# Power_Regulators_Digital_2.net
KiCad netlist of a schematic drawn in Altium Designer
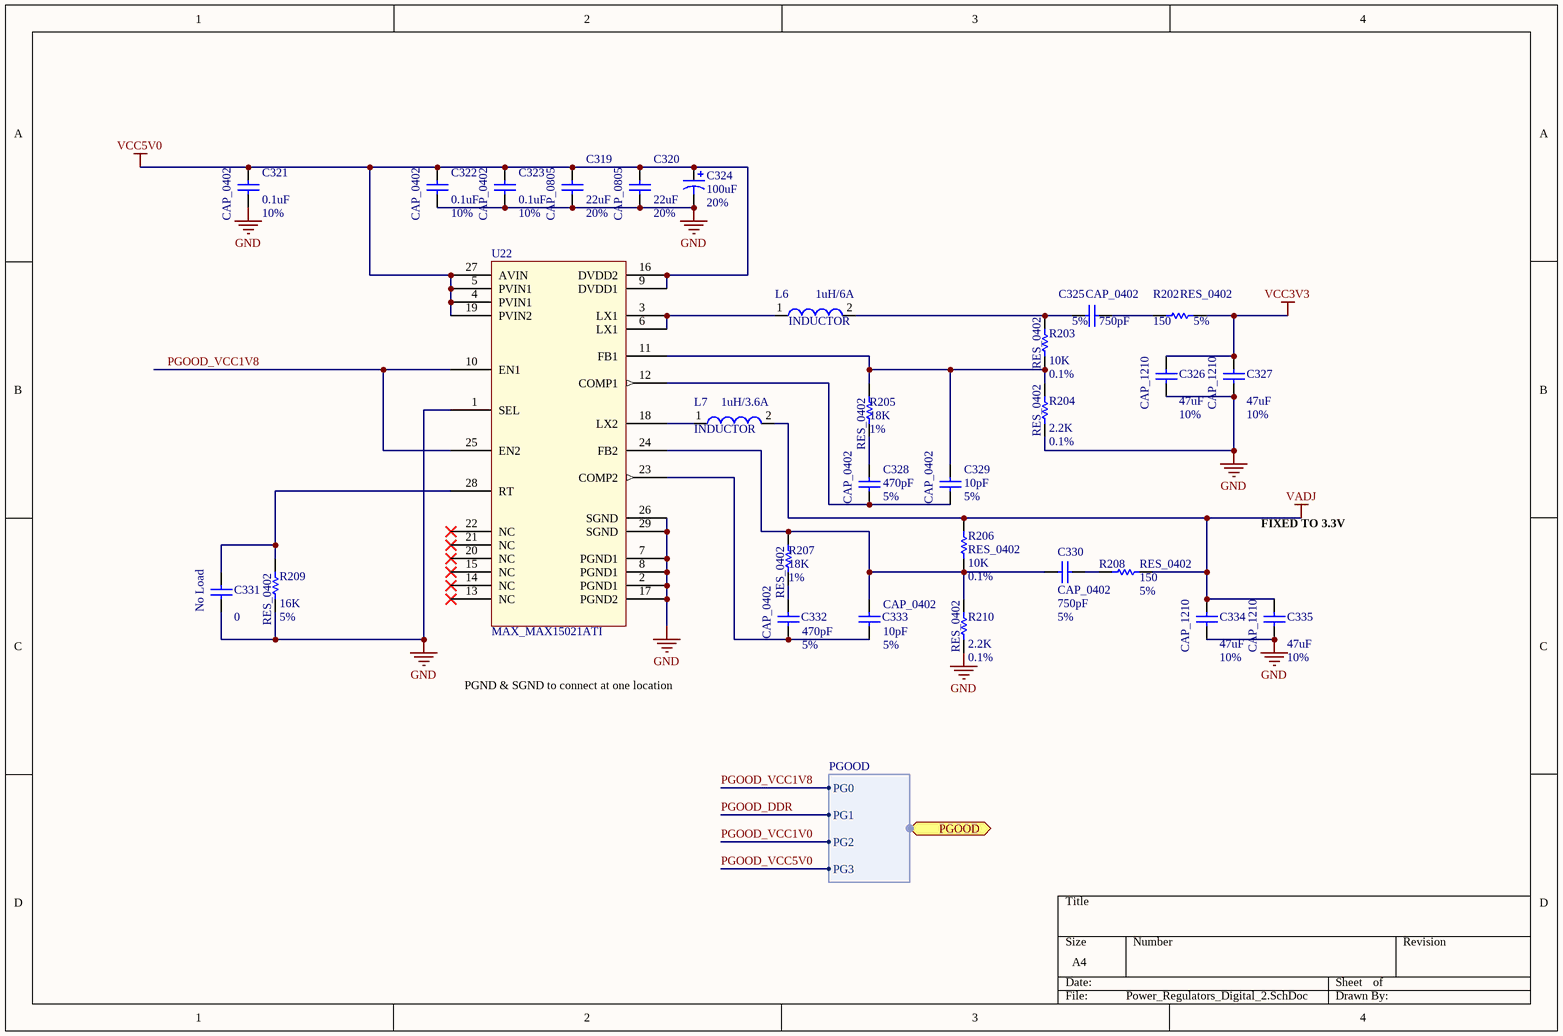
[diagram p0: Power_Regulators_Digital_2.SchDoc]

(export (version "E")
  (design (tool "Eeschema 10.0.6"))
  (components
    (comp (ref "C319")
      (value "CAP_0805")
      (footprint "CAPC0805(2012)75_N")
      (description "22uF, ceramic, 20%, 6.3V, X5R, 0805")
      (fields
        (field (name "ALTIUM_VALUE") "22uF")
        (field (name "TOLERANCE") "20%")
        (field (name "PART NUMBER") "JMK212BJ226MG-T")
        (field (name "MANUFACTURER") "Taiyo Yuden")
      )
      (libsource (lib "COMRAD_Database") (part "CAP_0805"))
    )
    (comp (ref "C320")
      (value "CAP_0805")
      (footprint "CAPC0805(2012)75_N")
      (description "22uF, ceramic, 20%, 6.3V, X5R, 0805")
      (fields
        (field (name "ALTIUM_VALUE") "22uF")
        (field (name "TOLERANCE") "20%")
        (field (name "PART NUMBER") "JMK212BJ226MG-T")
        (field (name "MANUFACTURER") "Taiyo Yuden")
      )
      (libsource (lib "COMRAD_Database") (part "CAP_0805"))
    )
    (comp (ref "C321")
      (value "CAP_0402")
      (footprint "CAPC0402(1005)60_N")
      (description "0.1uf, ceramic, 10%, 6.3V, X5R, 0402")
      (fields
        (field (name "ALTIUM_VALUE") "0.1uF")
        (field (name "TOLERANCE") "10%")
        (field (name "PART NUMBER") "C1005X5R0J104K")
        (field (name "MANUFACTURER") "TDK Corporation")
      )
      (libsource (lib "COMRAD_Database") (part "CAP_0402"))
    )
    (comp (ref "C322")
      (value "CAP_0402")
      (footprint "CAPC0402(1005)60_N")
      (description "0.1uf, ceramic, 10%, 6.3V, X5R, 0402")
      (fields
        (field (name "ALTIUM_VALUE") "0.1uF")
        (field (name "TOLERANCE") "10%")
        (field (name "PART NUMBER") "C1005X5R0J104K")
        (field (name "MANUFACTURER") "TDK Corporation")
      )
      (libsource (lib "COMRAD_Database") (part "CAP_0402"))
    )
    (comp (ref "C323")
      (value "CAP_0402")
      (footprint "CAPC0402(1005)60_N")
      (description "0.1uf, ceramic, 10%, 6.3V, X5R, 0402")
      (fields
        (field (name "ALTIUM_VALUE") "0.1uF")
        (field (name "TOLERANCE") "10%")
        (field (name "PART NUMBER") "C1005X5R0J104K")
        (field (name "MANUFACTURER") "TDK Corporation")
      )
      (libsource (lib "COMRAD_Database") (part "CAP_0402"))
    )
    (comp (ref "C324")
      (value "100uF")
      (footprint "Polarized_CAPC1210(3225)")
      (description "100uF, tantalum, 20% 10V, 1210")
      (fields
        (field (name "TOLERANCE") "20%")
        (field (name "PART NUMBER") "TLCT107M010XTA")
        (field (name "MANUFACTURER") "AVX Corporation")
      )
      (libsource (lib "COMRAD_Database") (part "Cap Pol1"))
    )
    (comp (ref "C325")
      (value "CAP_0402")
      (footprint "CAPC0402(1005)60_N")
      (description "750pF, ceramic, 5% 25V NP0, 0402")
      (fields
        (field (name "ALTIUM_VALUE") "750pF")
        (field (name "TOLERANCE") "5%")
        (field (name "PART NUMBER") "C0402C751J3GACTU")
        (field (name "MANUFACTURER") "Kemet")
      )
      (libsource (lib "COMRAD_Database") (part "CAP_0402"))
    )
    (comp (ref "C326")
      (value "CAP_1210")
      (footprint "CAPC1210(3225)100_N")
      (description "47uF, ceramic 10% 10V, X5R, 1210")
      (fields
        (field (name "ALTIUM_VALUE") "47uF")
        (field (name "TOLERANCE") "10%")
        (field (name "PART NUMBER") "GRM32ER61A476KE20L")
        (field (name "MANUFACTURER") "Murata Electronics North America")
      )
      (libsource (lib "COMRAD_Database") (part "CAP_1210"))
    )
    (comp (ref "C327")
      (value "CAP_1210")
      (footprint "CAPC1210(3225)100_N")
      (description "47uF, ceramic 10% 10V, X5R, 1210")
      (fields
        (field (name "ALTIUM_VALUE") "47uF")
        (field (name "TOLERANCE") "10%")
        (field (name "PART NUMBER") "GRM32ER61A476KE20L")
        (field (name "MANUFACTURER") "Murata Electronics North America")
      )
      (libsource (lib "COMRAD_Database") (part "CAP_1210"))
    )
    (comp (ref "C328")
      (value "CAP_0402")
      (footprint "CAPC0402(1005)60_N")
      (description "470pF, ceramic, 5%, 25V, X7R, 0402")
      (fields
        (field (name "ALTIUM_VALUE") "470pF")
        (field (name "TOLERANCE") "5%")
        (field (name "PART NUMBER") "ECJ-0EB1E471K")
        (field (name "MANUFACTURER") "Panasonic-ECG")
      )
      (libsource (lib "COMRAD_Database") (part "CAP_0402"))
    )
    (comp (ref "C329")
      (value "CAP_0402")
      (footprint "CAPC0402(1005)60_N")
      (description "10pF, ceramic, 5%, 50V, NP0, 0402")
      (fields
        (field (name "ALTIUM_VALUE") "10pF")
        (field (name "TOLERANCE") "5%")
        (field (name "PART NUMBER") "VJ0402A100JXACW1BC")
        (field (name "MANUFACTURER") "BC COMPONENTS")
      )
      (libsource (lib "COMRAD_Database") (part "CAP_0402"))
    )
    (comp (ref "C330")
      (value "CAP_0402")
      (footprint "CAPC0402(1005)60_N")
      (description "750pF, ceramic, 5% 25V NP0, 0402")
      (fields
        (field (name "ALTIUM_VALUE") "750pF")
        (field (name "TOLERANCE") "5%")
        (field (name "PART NUMBER") "C0402C751J3GACTU")
        (field (name "MANUFACTURER") "Kemet")
      )
      (libsource (lib "COMRAD_Database") (part "CAP_0402"))
    )
    (comp (ref "C331")
      (value "0")
      (footprint "CAPC0201(0603)33_N:CAPC0201(0603)33_N")
      (description "Generic Capacitor")
      (fields
        (field (name "PART NUMBER") "No Load_0")
        (field (name "MANUFACTURER") "No Load")
        (field (name "Comment") "CAP_0201")
      )
      (libsource (lib "COMRAD_Database") (part "CAP_0201"))
    )
    (comp (ref "C332")
      (value "CAP_0402")
      (footprint "CAPC0402(1005)60_N")
      (description "470pF, ceramic, 5%, 25V, X7R, 0402")
      (fields
        (field (name "ALTIUM_VALUE") "470pF")
        (field (name "TOLERANCE") "5%")
        (field (name "PART NUMBER") "ECJ-0EB1E471K")
        (field (name "MANUFACTURER") "Panasonic-ECG")
      )
      (libsource (lib "COMRAD_Database") (part "CAP_0402"))
    )
    (comp (ref "C333")
      (value "CAP_0402")
      (footprint "CAPC0402(1005)60_N")
      (description "10pF, ceramic, 5%, 50V, NP0, 0402")
      (fields
        (field (name "ALTIUM_VALUE") "10pF")
        (field (name "TOLERANCE") "5%")
        (field (name "PART NUMBER") "VJ0402A100JXACW1BC")
        (field (name "MANUFACTURER") "BC COMPONENTS")
      )
      (libsource (lib "COMRAD_Database") (part "CAP_0402"))
    )
    (comp (ref "C334")
      (value "CAP_1210")
      (footprint "CAPC1210(3225)100_N")
      (description "47uF, ceramic 10% 10V, X5R, 1210")
      (fields
        (field (name "ALTIUM_VALUE") "47uF")
        (field (name "TOLERANCE") "10%")
        (field (name "PART NUMBER") "GRM32ER61A476KE20L")
        (field (name "MANUFACTURER") "Murata Electronics North America")
      )
      (libsource (lib "COMRAD_Database") (part "CAP_1210"))
    )
    (comp (ref "C335")
      (value "CAP_1210")
      (footprint "CAPC1210(3225)100_N")
      (description "47uF, ceramic 10% 10V, X5R, 1210")
      (fields
        (field (name "ALTIUM_VALUE") "47uF")
        (field (name "TOLERANCE") "10%")
        (field (name "PART NUMBER") "GRM32ER61A476KE20L")
        (field (name "MANUFACTURER") "Murata Electronics North America")
      )
      (libsource (lib "COMRAD_Database") (part "CAP_1210"))
    )
    (comp (ref "L6")
      (value "INDUCTOR")
      (footprint "Inductor_SRN6045-Series_2-PIN")
      (description "SRN6045-1R0Y, 1uH 4.2A-8.5A, CDRH6D38")
      (fields
        (field (name "ALTIUM_VALUE") "1uH/6A")
        (field (name "PART NUMBER") "SRN6045-1R0Y")
        (field (name "MANUFACTURER") "Bourns")
      )
      (libsource (lib "COMRAD_Database") (part "INDUCTOR"))
    )
    (comp (ref "L7")
      (value "INDUCTOR")
      (footprint "Inductor_NRS5020T1R0NMGJ_2-PIN")
      (description "NRS5020T1R0NMGJ, 1uH 3.6A, 5020")
      (fields
        (field (name "ALTIUM_VALUE") "1uH/3.6A")
        (field (name "PART NUMBER") "NRS5020T1R0NMGJ")
        (field (name "MANUFACTURER") "Taiyo Yuden")
      )
      (libsource (lib "COMRAD_Database") (part "INDUCTOR"))
    )
    (comp (ref "R202")
      (value "RES_0402")
      (footprint "RESC0402(1005)_N")
      (description "150 ohm, 5% 1/16W, 0402")
      (fields
        (field (name "ALTIUM_VALUE") "150")
        (field (name "TOLERANCE") "5%")
        (field (name "PART NUMBER") "RC0402JR-07150RL")
        (field (name "MANUFACTURER") "Yageo America")
      )
      (libsource (lib "COMRAD_Database") (part "RES_0402"))
    )
    (comp (ref "R203")
      (value "RES_0402")
      (footprint "RESC0402(1005)_N")
      (description "10K ohm, 0.1% 1/16W, 0402")
      (fields
        (field (name "ALTIUM_VALUE") "10K")
        (field (name "TOLERANCE") "0.1%")
        (field (name "PART NUMBER") "ERA-2AEB103X")
        (field (name "MANUFACTURER") "Panasonic - ECG")
      )
      (libsource (lib "COMRAD_Database") (part "RES_0402"))
    )
    (comp (ref "R204")
      (value "RES_0402")
      (footprint "RESC0402(1005)_N")
      (description "2.2K ohm, 0.1% 1/16W, 0402")
      (fields
        (field (name "ALTIUM_VALUE") "2.2K")
        (field (name "TOLERANCE") "0.1%")
        (field (name "PART NUMBER") "ERA-2AEB222X")
        (field (name "MANUFACTURER") "Panasonic - ECG")
      )
      (libsource (lib "COMRAD_Database") (part "RES_0402"))
    )
    (comp (ref "R205")
      (value "RES_0402")
      (footprint "RESC0402(1005)_N")
      (description "18K ohm, 1% 1/16W, 0402")
      (fields
        (field (name "ALTIUM_VALUE") "18K")
        (field (name "TOLERANCE") "1%")
        (field (name "PART NUMBER") "MCR01MZPF1802")
        (field (name "MANUFACTURER") "ROHM")
      )
      (libsource (lib "COMRAD_Database") (part "RES_0402"))
    )
    (comp (ref "R206")
      (value "RES_0402")
      (footprint "RESC0402(1005)_N")
      (description "10K ohm, 0.1% 1/16W, 0402")
      (fields
        (field (name "ALTIUM_VALUE") "10K")
        (field (name "TOLERANCE") "0.1%")
        (field (name "PART NUMBER") "ERA-2AEB103X")
        (field (name "MANUFACTURER") "Panasonic - ECG")
      )
      (libsource (lib "COMRAD_Database") (part "RES_0402"))
    )
    (comp (ref "R207")
      (value "RES_0402")
      (footprint "RESC0402(1005)_N")
      (description "18K ohm, 1% 1/16W, 0402")
      (fields
        (field (name "ALTIUM_VALUE") "18K")
        (field (name "TOLERANCE") "1%")
        (field (name "PART NUMBER") "MCR01MZPF1802")
        (field (name "MANUFACTURER") "ROHM")
      )
      (libsource (lib "COMRAD_Database") (part "RES_0402"))
    )
    (comp (ref "R208")
      (value "RES_0402")
      (footprint "RESC0402(1005)_N")
      (description "150 ohm, 5% 1/16W, 0402")
      (fields
        (field (name "ALTIUM_VALUE") "150")
        (field (name "TOLERANCE") "5%")
        (field (name "PART NUMBER") "RC0402JR-07150RL")
        (field (name "MANUFACTURER") "Yageo America")
      )
      (libsource (lib "COMRAD_Database") (part "RES_0402"))
    )
    (comp (ref "R209")
      (value "RES_0402")
      (footprint "RESC0402(1005)_N")
      (description "16K ohm, 5% 1/16W, 0402")
      (fields
        (field (name "ALTIUM_VALUE") "16K")
        (field (name "TOLERANCE") "5%")
        (field (name "PART NUMBER") "CRCW040216K0JNED")
        (field (name "MANUFACTURER") "Vishay/Dale")
      )
      (libsource (lib "COMRAD_Database") (part "RES_0402"))
    )
    (comp (ref "R210")
      (value "RES_0402")
      (footprint "RESC0402(1005)_N")
      (description "2.2K ohm, 0.1% 1/16W, 0402")
      (fields
        (field (name "ALTIUM_VALUE") "2.2K")
        (field (name "TOLERANCE") "0.1%")
        (field (name "PART NUMBER") "ERA-2AEB222X")
        (field (name "MANUFACTURER") "Panasonic - ECG")
      )
      (libsource (lib "COMRAD_Database") (part "RES_0402"))
    )
    (comp (ref "U22")
      (value "MAX_MAX15021ATI")
      (footprint "MAX_MAX15021ATI_28TQFN_T2855-6")
      (description "MAX15021ATI, 4A/2A, 4MHz, Step-Down DC-DC Regulator, TQFN28")
      (fields
        (field (name "PART NUMBER") "MAX15021ATI+")
        (field (name "MANUFACTURER") "Maxim Integrated Products")
      )
      (libsource (lib "COMRAD_Database") (part "MAX_MAX15021ATI"))
    )
  )
  (nets
    (net (code "4") (name "/PGOOD_VCC1V8") (class "Default")
      (node (ref "U22") (pin "10") (pinfunction "EN1_10") (pintype "power_in"))
      (node (ref "U22") (pin "25") (pinfunction "EN2_25") (pintype "power_in"))
    )
    (net (code "7") (name "GND") (class "Default")
      (node (ref "C319") (pin "1") (pinfunction "1_1") (pintype "passive"))
      (node (ref "C320") (pin "1") (pinfunction "1_1") (pintype "passive"))
      (node (ref "C321") (pin "1") (pinfunction "1_1") (pintype "passive"))
      (node (ref "C322") (pin "1") (pinfunction "1_1") (pintype "passive"))
      (node (ref "C323") (pin "1") (pinfunction "1_1") (pintype "passive"))
      (node (ref "C324") (pin "2") (pinfunction "2_2") (pintype "passive"))
      (node (ref "C326") (pin "1") (pinfunction "1_1") (pintype "passive"))
      (node (ref "C327") (pin "1") (pinfunction "1_1") (pintype "passive"))
      (node (ref "C331") (pin "1") (pinfunction "1_1") (pintype "passive"))
      (node (ref "C334") (pin "1") (pinfunction "1_1") (pintype "passive"))
      (node (ref "C335") (pin "1") (pinfunction "1_1") (pintype "passive"))
      (node (ref "R204") (pin "1") (pinfunction "1_1") (pintype "passive"))
      (node (ref "R209") (pin "2") (pinfunction "2_2") (pintype "passive"))
      (node (ref "R210") (pin "1") (pinfunction "1_1") (pintype "passive"))
      (node (ref "U22") (pin "1") (pinfunction "SEL_1") (pintype "power_in"))
      (node (ref "U22") (pin "17") (pinfunction "PGND2_17") (pintype "power_in"))
      (node (ref "U22") (pin "2") (pinfunction "PGND1_2") (pintype "power_in"))
      (node (ref "U22") (pin "26") (pinfunction "SGND_26") (pintype "power_in"))
      (node (ref "U22") (pin "29") (pinfunction "SGND_29") (pintype "power_in"))
      (node (ref "U22") (pin "7") (pinfunction "PGND1_7") (pintype "power_in"))
      (node (ref "U22") (pin "8") (pinfunction "PGND1_8") (pintype "power_in"))
    )
    (net (code "8") (name "Net-(C325-Pad1)") (class "Default")
      (node (ref "C325") (pin "1") (pinfunction "1_1") (pintype "passive"))
      (node (ref "L6") (pin "2") (pinfunction "2_2") (pintype "passive"))
      (node (ref "R203") (pin "2") (pinfunction "2_2") (pintype "passive"))
    )
    (net (code "9") (name "Net-(C325-Pad2)") (class "Default")
      (node (ref "C325") (pin "2") (pinfunction "2_2") (pintype "passive"))
      (node (ref "R202") (pin "1") (pinfunction "1_1") (pintype "passive"))
    )
    (net (code "10") (name "Net-(C328-Pad2)") (class "Default")
      (node (ref "C328") (pin "2") (pinfunction "2_2") (pintype "passive"))
      (node (ref "R205") (pin "1") (pinfunction "1_1") (pintype "passive"))
    )
    (net (code "11") (name "Net-(C330-Pad2)") (class "Default")
      (node (ref "C330") (pin "2") (pinfunction "2_2") (pintype "passive"))
      (node (ref "R208") (pin "1") (pinfunction "1_1") (pintype "passive"))
    )
    (net (code "12") (name "Net-(C332-Pad2)") (class "Default")
      (node (ref "C332") (pin "2") (pinfunction "2_2") (pintype "passive"))
      (node (ref "R207") (pin "1") (pinfunction "1_1") (pintype "passive"))
    )
    (net (code "13") (name "Net-(L6-Pad1)") (class "Default")
      (node (ref "L6") (pin "1") (pinfunction "1_1") (pintype "passive"))
      (node (ref "U22") (pin "3") (pinfunction "LX1_3") (pintype "power_in"))
      (node (ref "U22") (pin "6") (pinfunction "LX1_6") (pintype "power_in"))
    )
    (net (code "14") (name "Net-(U22-COMP1)") (class "Default")
      (node (ref "C328") (pin "1") (pinfunction "1_1") (pintype "passive"))
      (node (ref "C329") (pin "1") (pinfunction "1_1") (pintype "passive"))
      (node (ref "U22") (pin "12") (pinfunction "COMP1_12") (pintype "output"))
    )
    (net (code "15") (name "Net-(U22-COMP2)") (class "Default")
      (node (ref "C332") (pin "1") (pinfunction "1_1") (pintype "passive"))
      (node (ref "C333") (pin "1") (pinfunction "1_1") (pintype "passive"))
      (node (ref "U22") (pin "23") (pinfunction "COMP2_23") (pintype "output"))
    )
    (net (code "16") (name "Net-(U22-FB1)") (class "Default")
      (node (ref "C329") (pin "2") (pinfunction "2_2") (pintype "passive"))
      (node (ref "R203") (pin "1") (pinfunction "1_1") (pintype "passive"))
      (node (ref "R204") (pin "2") (pinfunction "2_2") (pintype "passive"))
      (node (ref "R205") (pin "2") (pinfunction "2_2") (pintype "passive"))
      (node (ref "U22") (pin "11") (pinfunction "FB1_11") (pintype "power_in"))
    )
    (net (code "17") (name "Net-(U22-FB2)") (class "Default")
      (node (ref "C330") (pin "1") (pinfunction "1_1") (pintype "passive"))
      (node (ref "C333") (pin "2") (pinfunction "2_2") (pintype "passive"))
      (node (ref "R206") (pin "1") (pinfunction "1_1") (pintype "passive"))
      (node (ref "R207") (pin "2") (pinfunction "2_2") (pintype "passive"))
      (node (ref "R210") (pin "2") (pinfunction "2_2") (pintype "passive"))
      (node (ref "U22") (pin "24") (pinfunction "FB2_24") (pintype "power_in"))
    )
    (net (code "18") (name "Net-(U22-LX2)") (class "Default")
      (node (ref "L7") (pin "1") (pinfunction "1_1") (pintype "passive"))
      (node (ref "U22") (pin "18") (pinfunction "LX2_18") (pintype "power_in"))
    )
    (net (code "19") (name "Net-(U22-RT)") (class "Default")
      (node (ref "C331") (pin "2") (pinfunction "2_2") (pintype "passive"))
      (node (ref "R209") (pin "1") (pinfunction "1_1") (pintype "passive"))
      (node (ref "U22") (pin "28") (pinfunction "RT_28") (pintype "power_in"))
    )
    (net (code "20") (name "VADJ") (class "Default")
      (node (ref "C334") (pin "2") (pinfunction "2_2") (pintype "passive"))
      (node (ref "C335") (pin "2") (pinfunction "2_2") (pintype "passive"))
      (node (ref "L7") (pin "2") (pinfunction "2_2") (pintype "passive"))
      (node (ref "R206") (pin "2") (pinfunction "2_2") (pintype "passive"))
      (node (ref "R208") (pin "2") (pinfunction "2_2") (pintype "passive"))
    )
    (net (code "21") (name "VCC3V3") (class "Default")
      (node (ref "C326") (pin "2") (pinfunction "2_2") (pintype "passive"))
      (node (ref "C327") (pin "2") (pinfunction "2_2") (pintype "passive"))
      (node (ref "R202") (pin "2") (pinfunction "2_2") (pintype "passive"))
    )
    (net (code "22") (name "VCC5V0") (class "Default")
      (node (ref "C319") (pin "2") (pinfunction "2_2") (pintype "passive"))
      (node (ref "C320") (pin "2") (pinfunction "2_2") (pintype "passive"))
      (node (ref "C321") (pin "2") (pinfunction "2_2") (pintype "passive"))
      (node (ref "C322") (pin "2") (pinfunction "2_2") (pintype "passive"))
      (node (ref "C323") (pin "2") (pinfunction "2_2") (pintype "passive"))
      (node (ref "C324") (pin "1") (pinfunction "1_1") (pintype "passive"))
      (node (ref "U22") (pin "16") (pinfunction "DVDD2_16") (pintype "power_in"))
      (node (ref "U22") (pin "19") (pinfunction "PVIN2_19") (pintype "power_in"))
      (node (ref "U22") (pin "27") (pinfunction "AVIN_27") (pintype "power_in"))
      (node (ref "U22") (pin "4") (pinfunction "PVIN1_4") (pintype "power_in"))
      (node (ref "U22") (pin "5") (pinfunction "PVIN1_5") (pintype "power_in"))
      (node (ref "U22") (pin "9") (pinfunction "DVDD1_9") (pintype "power_in"))
    )
    (net (code "23") (name "unconnected-(U22-NC-Pad13)") (class "Default")
      (node (ref "U22") (pin "13") (pinfunction "NC_13") (pintype "power_in+no_connect"))
    )
    (net (code "24") (name "unconnected-(U22-NC-Pad14)") (class "Default")
      (node (ref "U22") (pin "14") (pinfunction "NC_14") (pintype "power_in+no_connect"))
    )
    (net (code "25") (name "unconnected-(U22-NC-Pad15)") (class "Default")
      (node (ref "U22") (pin "15") (pinfunction "NC_15") (pintype "power_in+no_connect"))
    )
    (net (code "26") (name "unconnected-(U22-NC-Pad20)") (class "Default")
      (node (ref "U22") (pin "20") (pinfunction "NC_20") (pintype "power_in+no_connect"))
    )
    (net (code "27") (name "unconnected-(U22-NC-Pad21)") (class "Default")
      (node (ref "U22") (pin "21") (pinfunction "NC_21") (pintype "power_in+no_connect"))
    )
    (net (code "28") (name "unconnected-(U22-NC-Pad22)") (class "Default")
      (node (ref "U22") (pin "22") (pinfunction "NC_22") (pintype "power_in+no_connect"))
    )
  )
)
